# TSOC_GROVEY_I2CHUB_R1_1.net
KiCad netlist of a schematic drawn in EAGLE
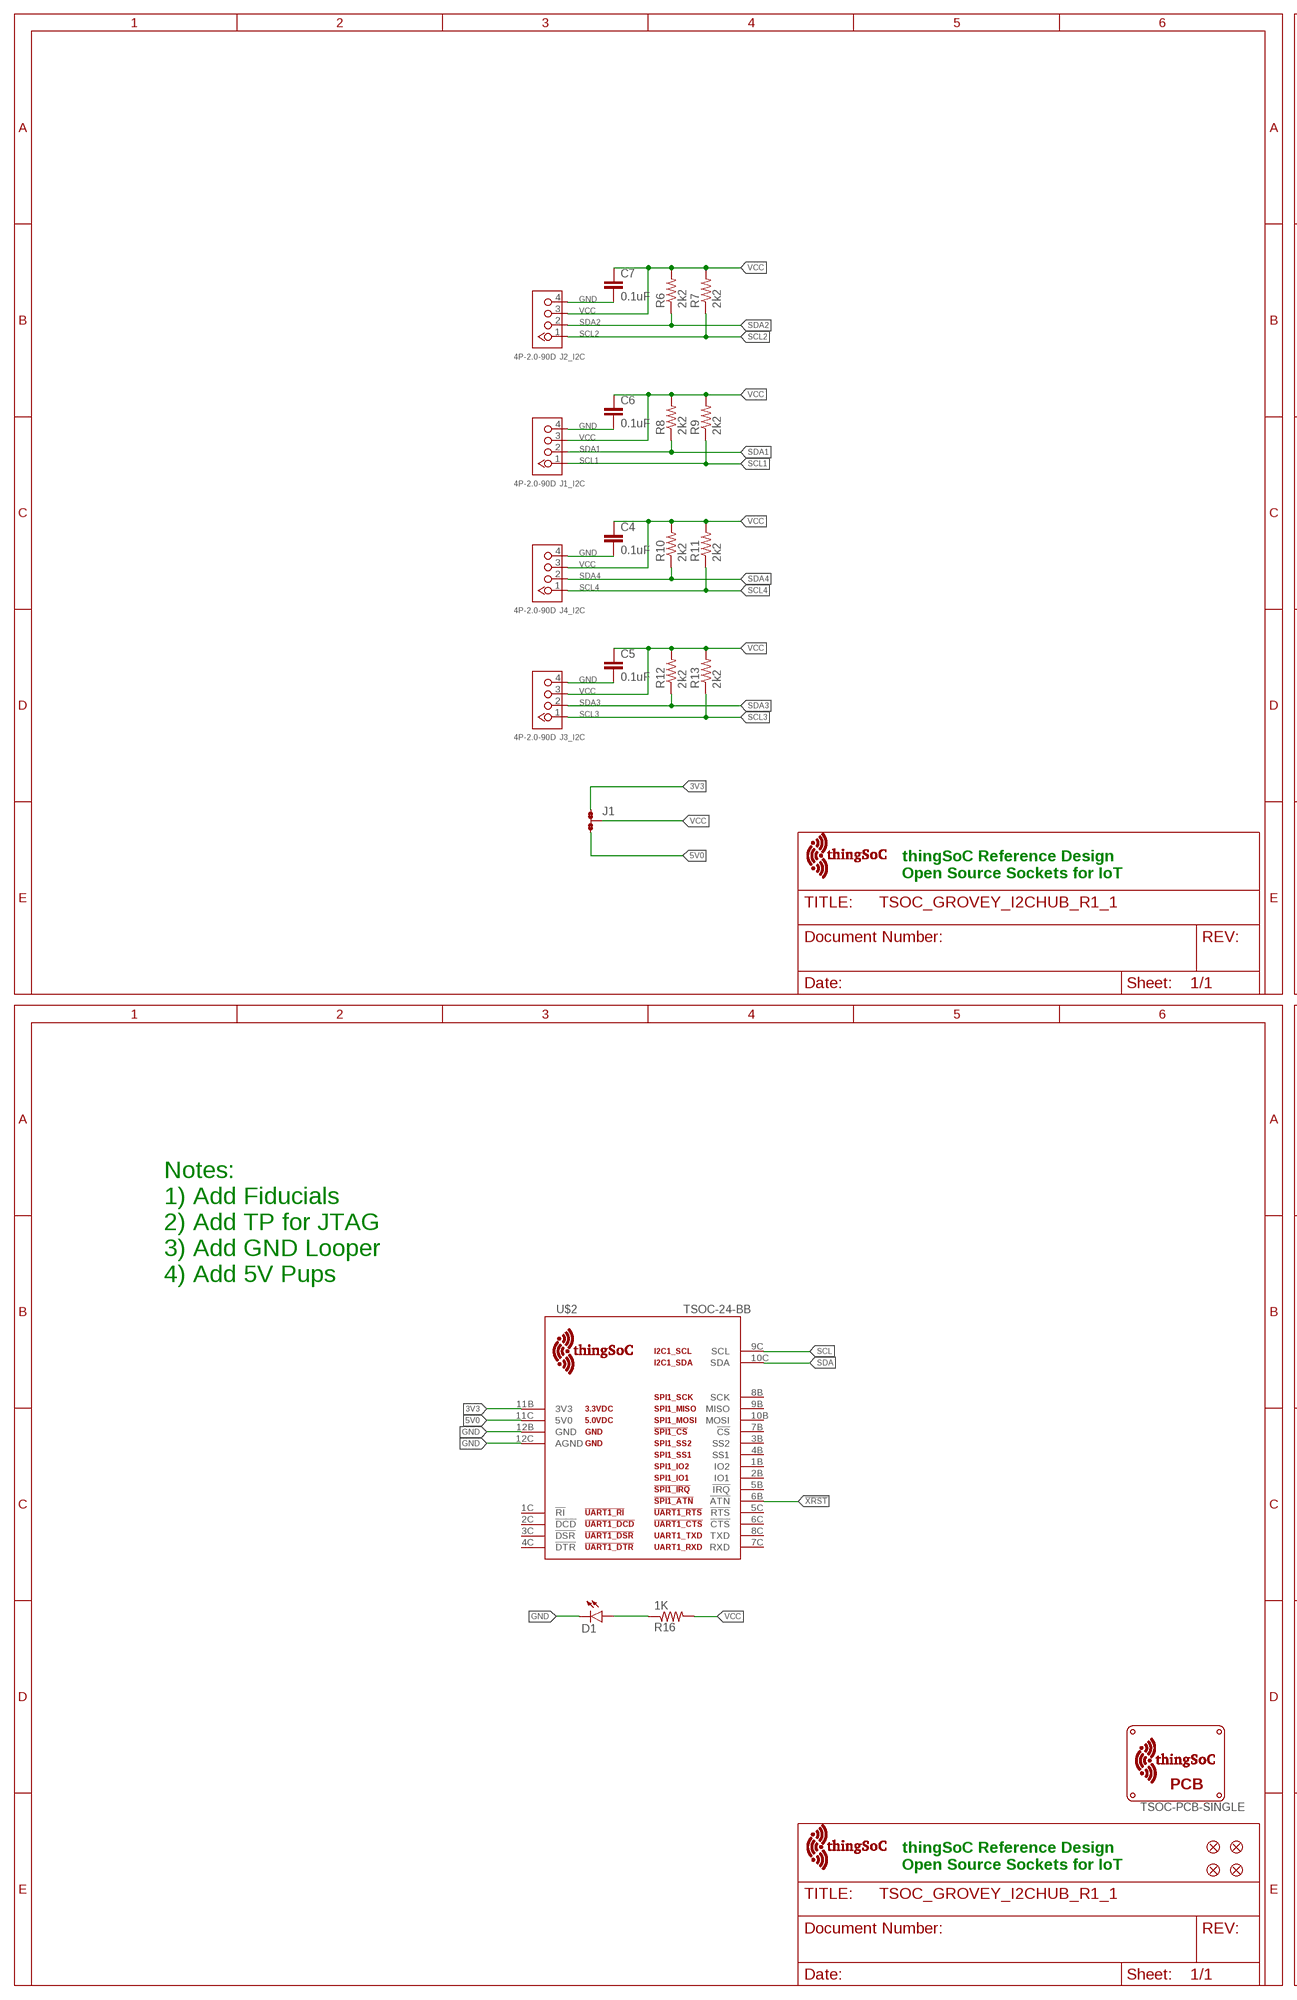
[diagram p0: schematic, sheet 1, part 1 of 2]
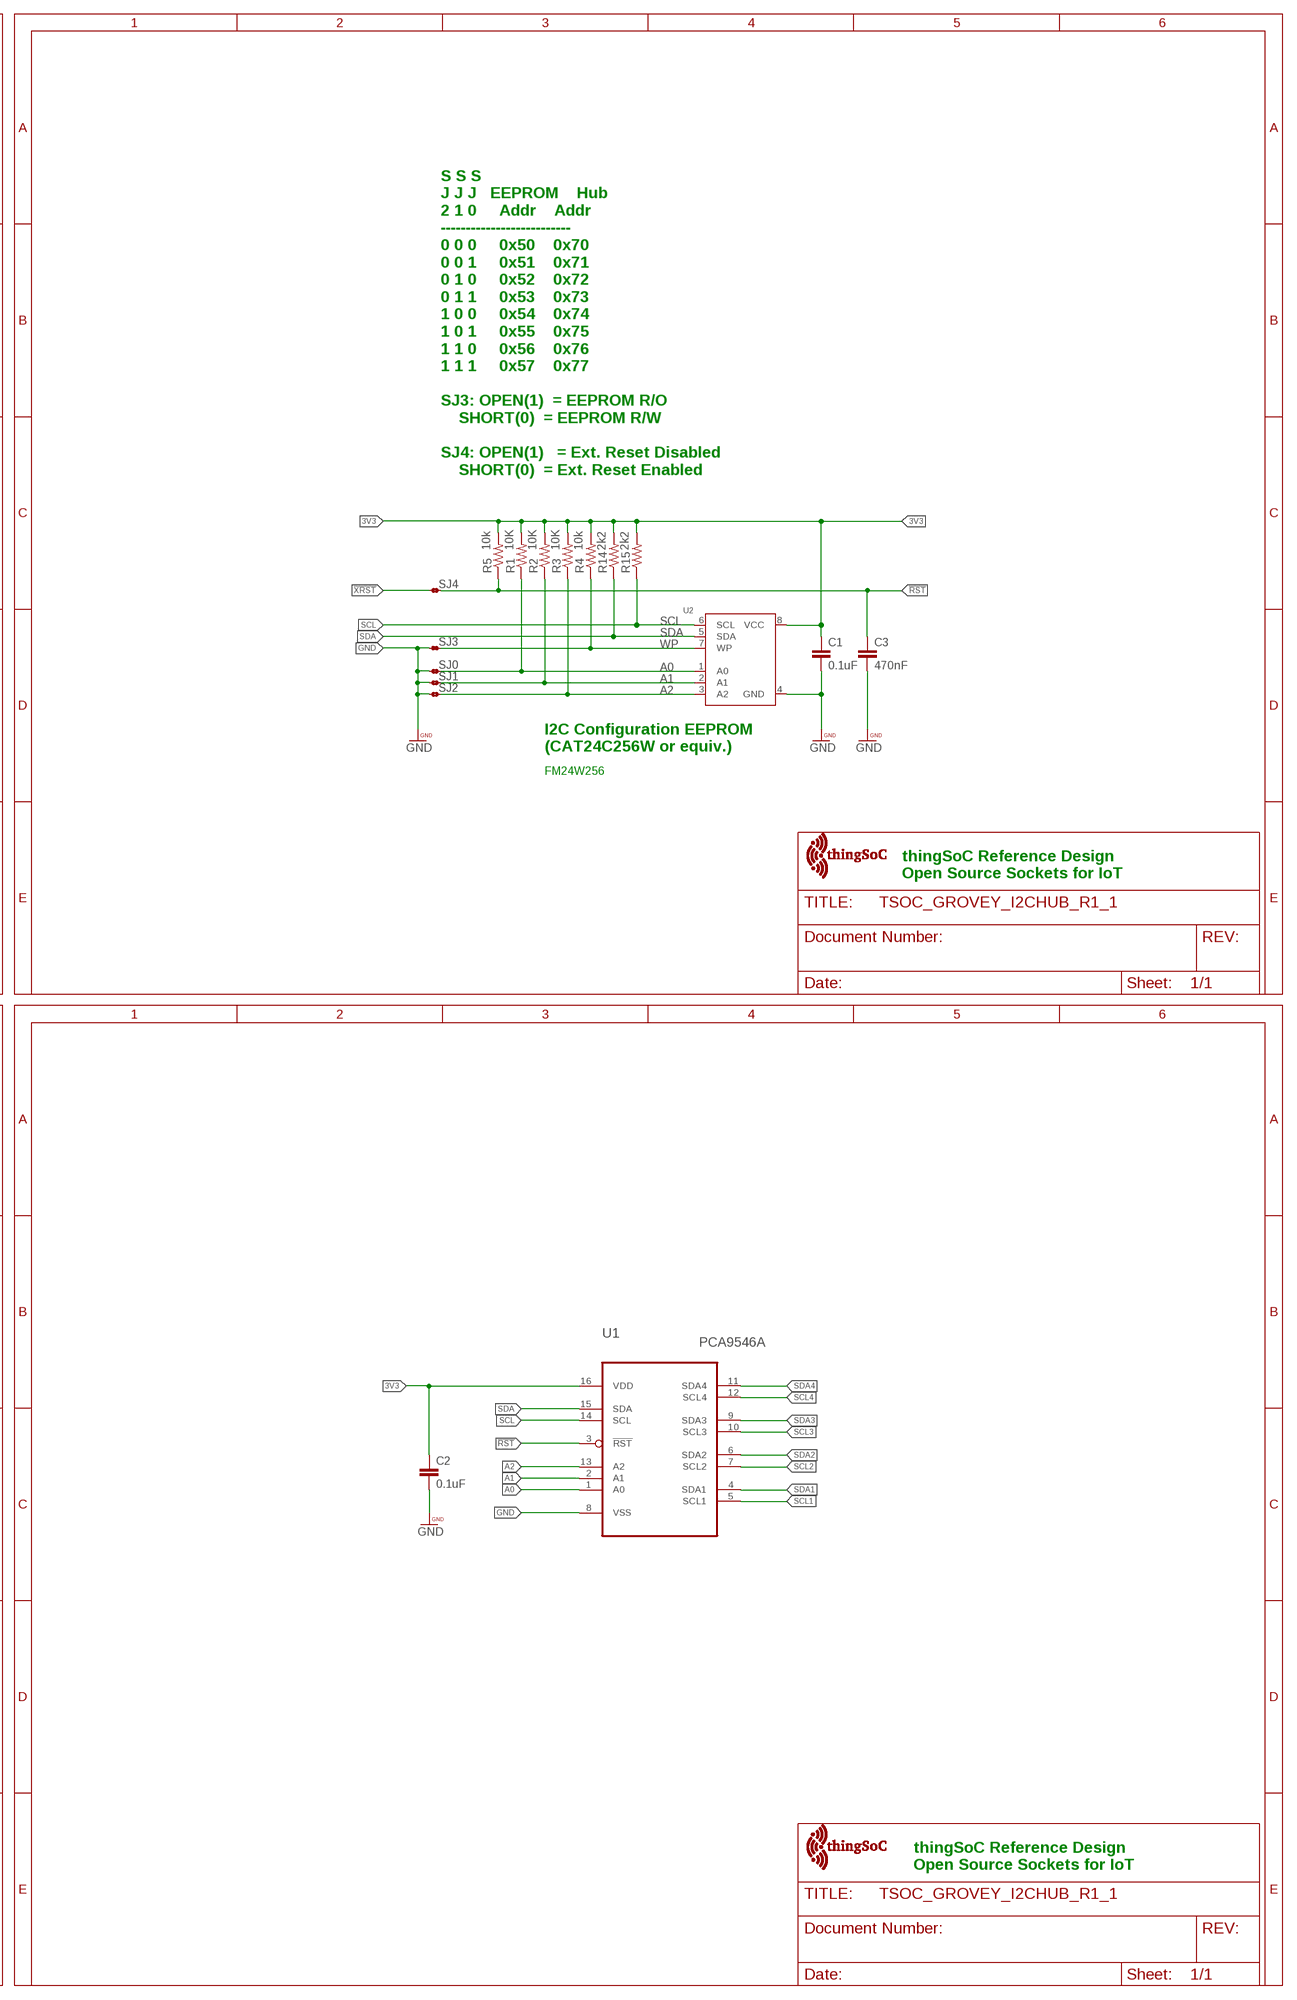
[diagram p1: schematic, sheet 1, part 2 of 2]

(export (version "E")
  (design (tool "Eeschema 10.0.6"))
  (components
    (comp (ref "C1")
      (value "0.1uF")
      (footprint "eagle-import:0603-CAP")
      (libsource (lib "eagle-import") (part "CAP0603-CAP"))
    )
    (comp (ref "C2")
      (value "0.1uF")
      (footprint "eagle-import:0603-CAP")
      (libsource (lib "eagle-import") (part "CAP0603-CAP"))
    )
    (comp (ref "C3")
      (value "470nF")
      (footprint "eagle-import:0603-CAP")
      (libsource (lib "eagle-import") (part "CAP0603-CAP"))
    )
    (comp (ref "C4")
      (value "0.1uF")
      (footprint "eagle-import:0603-CAP")
      (libsource (lib "eagle-import") (part "CAP0603-CAP"))
    )
    (comp (ref "C5")
      (value "0.1uF")
      (footprint "eagle-import:0603-CAP")
      (libsource (lib "eagle-import") (part "CAP0603-CAP"))
    )
    (comp (ref "C6")
      (value "0.1uF")
      (footprint "eagle-import:0603-CAP")
      (libsource (lib "eagle-import") (part "CAP0603-CAP"))
    )
    (comp (ref "C7")
      (value "0.1uF")
      (footprint "eagle-import:0603-CAP")
      (libsource (lib "eagle-import") (part "CAP0603-CAP"))
    )
    (comp (ref "D1")
      (value "LED0603")
      (footprint "eagle-import:LED-0603")
      (libsource (lib "eagle-import") (part "LED0603"))
    )
    (comp (ref "FID1")
      (value "FIDUCIALUFIDUCIAL")
      (footprint "eagle-import:MICRO-FIDUCIAL")
      (libsource (lib "eagle-import") (part "FIDUCIALUFIDUCIAL"))
    )
    (comp (ref "FID2")
      (value "FIDUCIALUFIDUCIAL")
      (footprint "eagle-import:MICRO-FIDUCIAL")
      (libsource (lib "eagle-import") (part "FIDUCIALUFIDUCIAL"))
    )
    (comp (ref "FID3")
      (value "FIDUCIALUFIDUCIAL")
      (footprint "eagle-import:MICRO-FIDUCIAL")
      (libsource (lib "eagle-import") (part "FIDUCIALUFIDUCIAL"))
    )
    (comp (ref "FID4")
      (value "FIDUCIALUFIDUCIAL")
      (footprint "eagle-import:MICRO-FIDUCIAL")
      (libsource (lib "eagle-import") (part "FIDUCIALUFIDUCIAL"))
    )
    (comp (ref "J1")
      (value "JMP-3-NO-PTH")
      (footprint "eagle-import:JMP-3-NO-PTH-2.54")
      (libsource (lib "eagle-import") (part "JMP-3-NO-PTH"))
    )
    (comp (ref "J1_I2C")
      (value "4P-2.0-90D")
      (footprint "eagle-import:HW4-2.0-90D")
      (libsource (lib "eagle-import") (part "GROVE-CONNECTOR-DIP-90D(4P-2.0)"))
    )
    (comp (ref "J2_I2C")
      (value "4P-2.0-90D")
      (footprint "eagle-import:HW4-2.0-90D")
      (libsource (lib "eagle-import") (part "GROVE-CONNECTOR-DIP-90D(4P-2.0)"))
    )
    (comp (ref "J3_I2C")
      (value "4P-2.0-90D")
      (footprint "eagle-import:HW4-2.0-90D")
      (libsource (lib "eagle-import") (part "GROVE-CONNECTOR-DIP-90D(4P-2.0)"))
    )
    (comp (ref "J4_I2C")
      (value "4P-2.0-90D")
      (footprint "eagle-import:HW4-2.0-90D")
      (libsource (lib "eagle-import") (part "GROVE-CONNECTOR-DIP-90D(4P-2.0)"))
    )
    (comp (ref "R1")
      (value "10K")
      (footprint "eagle-import:0603-RES")
      (libsource (lib "eagle-import") (part "RESISTOR0603-RES"))
    )
    (comp (ref "R2")
      (value "10K")
      (footprint "eagle-import:0603-RES")
      (libsource (lib "eagle-import") (part "RESISTOR0603-RES"))
    )
    (comp (ref "R3")
      (value "10K")
      (footprint "eagle-import:0603-RES")
      (libsource (lib "eagle-import") (part "RESISTOR0603-RES"))
    )
    (comp (ref "R4")
      (value "10k")
      (footprint "eagle-import:0603-RES")
      (libsource (lib "eagle-import") (part "RESISTOR0603-RES"))
    )
    (comp (ref "R5")
      (value "10k")
      (footprint "eagle-import:0603-RES")
      (libsource (lib "eagle-import") (part "RESISTOR0603-RES"))
    )
    (comp (ref "R6")
      (value "2k2")
      (footprint "eagle-import:0603-RES")
      (libsource (lib "eagle-import") (part "RESISTOR0603-RES"))
    )
    (comp (ref "R7")
      (value "2k2")
      (footprint "eagle-import:0603-RES")
      (libsource (lib "eagle-import") (part "RESISTOR0603-RES"))
    )
    (comp (ref "R8")
      (value "2k2")
      (footprint "eagle-import:0603-RES")
      (libsource (lib "eagle-import") (part "RESISTOR0603-RES"))
    )
    (comp (ref "R9")
      (value "2k2")
      (footprint "eagle-import:0603-RES")
      (libsource (lib "eagle-import") (part "RESISTOR0603-RES"))
    )
    (comp (ref "R10")
      (value "2k2")
      (footprint "eagle-import:0603-RES")
      (libsource (lib "eagle-import") (part "RESISTOR0603-RES"))
    )
    (comp (ref "R11")
      (value "2k2")
      (footprint "eagle-import:0603-RES")
      (libsource (lib "eagle-import") (part "RESISTOR0603-RES"))
    )
    (comp (ref "R12")
      (value "2k2")
      (footprint "eagle-import:0603-RES")
      (libsource (lib "eagle-import") (part "RESISTOR0603-RES"))
    )
    (comp (ref "R13")
      (value "2k2")
      (footprint "eagle-import:0603-RES")
      (libsource (lib "eagle-import") (part "RESISTOR0603-RES"))
    )
    (comp (ref "R14")
      (value "2k2")
      (footprint "eagle-import:0603-RES")
      (libsource (lib "eagle-import") (part "RESISTOR0603-RES"))
    )
    (comp (ref "R15")
      (value "2k2")
      (footprint "eagle-import:0603-RES")
      (libsource (lib "eagle-import") (part "RESISTOR0603-RES"))
    )
    (comp (ref "R16")
      (value "1K")
      (footprint "eagle-import:0603-RES")
      (libsource (lib "eagle-import") (part "RESISTOR_SFE0603-RES"))
    )
    (comp (ref "SJ0")
      (value "JMP-2-NO")
      (footprint "eagle-import:JMP-2-NO")
      (libsource (lib "eagle-import") (part "JMP-2-NO"))
    )
    (comp (ref "SJ1")
      (value "JMP-2-NO")
      (footprint "eagle-import:JMP-2-NO")
      (libsource (lib "eagle-import") (part "JMP-2-NO"))
    )
    (comp (ref "SJ2")
      (value "JMP-2-NO")
      (footprint "eagle-import:JMP-2-NO")
      (libsource (lib "eagle-import") (part "JMP-2-NO"))
    )
    (comp (ref "SJ3")
      (value "JMP-2-NC")
      (footprint "eagle-import:JMP-2-NC")
      (libsource (lib "eagle-import") (part "JMP-2-NC"))
    )
    (comp (ref "SJ4")
      (value "JMP-2-NO")
      (footprint "eagle-import:JMP-2-NO")
      (libsource (lib "eagle-import") (part "JMP-2-NO"))
    )
    (comp (ref "U$1")
      (value "TSOC-PCB-SINGLE")
      (footprint "eagle-import:TSOC-BB-BRD-DIM")
      (libsource (lib "eagle-import") (part "TSOC-PCB-SINGLE"))
    )
    (comp (ref "U$2")
      (value "TSOC-24-BB")
      (footprint "eagle-import:TSOC-BB-S24")
      (libsource (lib "eagle-import") (part "TSOC-24-BB"))
    )
    (comp (ref "U$7")
      (value "TSOC-LOGO-SMALL")
      (footprint "eagle-import:TSOC-LOGO-SML")
      (libsource (lib "eagle-import") (part "TSOC-LOGO-SMALL"))
    )
    (comp (ref "U$9")
      (value "TSOC-LOGO-SMALL")
      (footprint "eagle-import:TSOC-LOGO-SML")
      (libsource (lib "eagle-import") (part "TSOC-LOGO-SMALL"))
    )
    (comp (ref "U$100")
      (value "TSOC-LOGO-SMALL")
      (footprint "eagle-import:TSOC-LOGO-SML")
      (libsource (lib "eagle-import") (part "TSOC-LOGO-SMALL"))
    )
    (comp (ref "U$101")
      (value "TSOC-LOGO-LRG")
      (footprint "eagle-import:TSOC-LOGO-LRG")
      (libsource (lib "eagle-import") (part "TSOC-LOGO-LRG"))
    )
    (comp (ref "U1")
      (value "PCA9546A")
      (footprint "eagle-import:SOP65P640X110-16N")
      (fields (field (name "MPN") "PCA9546APW,112"))
      (libsource (lib "eagle-import") (part "PCA9546A"))
    )
    (comp (ref "U2")
      (value "EEPROM_I2C_SOIC8_GENERIC")
      (footprint "eagle-import:SOIC8_150MIL")
      (libsource (lib "eagle-import") (part "EEPROM_I2C_SOIC8_GENERIC"))
    )
  )
  (nets
    (net (code "1") (name "/WP") (class "Default")
      (node (ref "R4") (pin "1") (pinfunction "1_1") (pintype "passive"))
      (node (ref "SJ3") (pin "2") (pinfunction "2_2") (pintype "passive"))
      (node (ref "U2") (pin "7") (pinfunction "WP_7") (pintype "input"))
    )
    (net (code "2") (name "/~{RST}") (class "Default")
      (node (ref "C3") (pin "1") (pinfunction "1_1") (pintype "passive"))
      (node (ref "R5") (pin "1") (pinfunction "1_1") (pintype "passive"))
      (node (ref "SJ4") (pin "1") (pinfunction "1_1") (pintype "passive"))
      (node (ref "U1") (pin "3") (pinfunction "~{RST}_3") (pintype "input"))
    )
    (net (code "3") (name "/~{XRST}") (class "Default")
      (node (ref "SJ4") (pin "2") (pinfunction "2_2") (pintype "passive"))
      (node (ref "U$2") (pin "6B") (pinfunction "~{ATN}_6B") (pintype "bidirectional"))
    )
    (net (code "4") (name "3V3") (class "Default")
      (node (ref "C1") (pin "1") (pinfunction "1_1") (pintype "passive"))
      (node (ref "C2") (pin "1") (pinfunction "1_1") (pintype "passive"))
      (node (ref "J1") (pin "1") (pinfunction "1_1") (pintype "passive"))
      (node (ref "R1") (pin "2") (pinfunction "2_2") (pintype "passive"))
      (node (ref "R14") (pin "2") (pinfunction "2_2") (pintype "passive"))
      (node (ref "R15") (pin "2") (pinfunction "2_2") (pintype "passive"))
      (node (ref "R2") (pin "2") (pinfunction "2_2") (pintype "passive"))
      (node (ref "R3") (pin "2") (pinfunction "2_2") (pintype "passive"))
      (node (ref "R4") (pin "2") (pinfunction "2_2") (pintype "passive"))
      (node (ref "R5") (pin "2") (pinfunction "2_2") (pintype "passive"))
      (node (ref "U$2") (pin "11B") (pinfunction "3V3_11B") (pintype "bidirectional"))
      (node (ref "U1") (pin "16") (pinfunction "VDD_16") (pintype "power_in"))
      (node (ref "U2") (pin "8") (pinfunction "VCC_8") (pintype "power_in"))
    )
    (net (code "5") (name "5V0") (class "Default")
      (node (ref "J1") (pin "3") (pinfunction "3_3") (pintype "passive"))
      (node (ref "U$2") (pin "11C") (pinfunction "5V0_11C") (pintype "bidirectional"))
    )
    (net (code "6") (name "A0") (class "Default")
      (node (ref "R1") (pin "1") (pinfunction "1_1") (pintype "passive"))
      (node (ref "SJ0") (pin "2") (pinfunction "2_2") (pintype "passive"))
      (node (ref "U1") (pin "1") (pinfunction "A0_1") (pintype "input"))
      (node (ref "U2") (pin "1") (pinfunction "A0_1") (pintype "input"))
    )
    (net (code "7") (name "A1") (class "Default")
      (node (ref "R2") (pin "1") (pinfunction "1_1") (pintype "passive"))
      (node (ref "SJ1") (pin "2") (pinfunction "2_2") (pintype "passive"))
      (node (ref "U1") (pin "2") (pinfunction "A1_2") (pintype "input"))
      (node (ref "U2") (pin "2") (pinfunction "A1_2") (pintype "input"))
    )
    (net (code "8") (name "A2") (class "Default")
      (node (ref "R3") (pin "1") (pinfunction "1_1") (pintype "passive"))
      (node (ref "SJ2") (pin "2") (pinfunction "2_2") (pintype "passive"))
      (node (ref "U1") (pin "13") (pinfunction "A2_13") (pintype "input"))
      (node (ref "U2") (pin "3") (pinfunction "A2_3") (pintype "input"))
    )
    (net (code "9") (name "GND") (class "Default")
      (node (ref "C1") (pin "2") (pinfunction "2_2") (pintype "passive"))
      (node (ref "C2") (pin "2") (pinfunction "2_2") (pintype "passive"))
      (node (ref "C3") (pin "2") (pinfunction "2_2") (pintype "passive"))
      (node (ref "C4") (pin "2") (pinfunction "2_2") (pintype "passive"))
      (node (ref "C5") (pin "2") (pinfunction "2_2") (pintype "passive"))
      (node (ref "C6") (pin "2") (pinfunction "2_2") (pintype "passive"))
      (node (ref "C7") (pin "2") (pinfunction "2_2") (pintype "passive"))
      (node (ref "D1") (pin "C") (pinfunction "C_C") (pintype "passive"))
      (node (ref "J1_I2C") (pin "4") (pinfunction "4_4") (pintype "bidirectional"))
      (node (ref "J2_I2C") (pin "4") (pinfunction "4_4") (pintype "bidirectional"))
      (node (ref "J3_I2C") (pin "4") (pinfunction "4_4") (pintype "bidirectional"))
      (node (ref "J4_I2C") (pin "4") (pinfunction "4_4") (pintype "bidirectional"))
      (node (ref "SJ0") (pin "1") (pinfunction "1_1") (pintype "passive"))
      (node (ref "SJ1") (pin "1") (pinfunction "1_1") (pintype "passive"))
      (node (ref "SJ2") (pin "1") (pinfunction "1_1") (pintype "passive"))
      (node (ref "SJ3") (pin "1") (pinfunction "1_1") (pintype "passive"))
      (node (ref "U$2") (pin "12B") (pinfunction "GND_12B") (pintype "bidirectional"))
      (node (ref "U$2") (pin "12C") (pinfunction "AGND_12C") (pintype "bidirectional"))
      (node (ref "U1") (pin "8") (pinfunction "VSS_8") (pintype "passive"))
      (node (ref "U2") (pin "4") (pinfunction "GND_4") (pintype "power_in"))
    )
    (net (code "10") (name "Net-(D1-PadA)") (class "Default")
      (node (ref "D1") (pin "A") (pinfunction "A_A") (pintype "passive"))
      (node (ref "R16") (pin "1") (pinfunction "1_1") (pintype "passive"))
    )
    (net (code "11") (name "SCL") (class "Default")
      (node (ref "R15") (pin "1") (pinfunction "1_1") (pintype "passive"))
      (node (ref "U$2") (pin "9C") (pinfunction "SCL_9C") (pintype "bidirectional"))
      (node (ref "U1") (pin "14") (pinfunction "SCL_14") (pintype "bidirectional"))
      (node (ref "U2") (pin "6") (pinfunction "SCL_6") (pintype "input"))
    )
    (net (code "12") (name "SCL1") (class "Default")
      (node (ref "J1_I2C") (pin "1") (pinfunction "1_1") (pintype "bidirectional"))
      (node (ref "R9") (pin "1") (pinfunction "1_1") (pintype "passive"))
      (node (ref "U1") (pin "5") (pinfunction "SCL1_5") (pintype "input"))
    )
    (net (code "13") (name "SCL2") (class "Default")
      (node (ref "J2_I2C") (pin "1") (pinfunction "1_1") (pintype "bidirectional"))
      (node (ref "R7") (pin "1") (pinfunction "1_1") (pintype "passive"))
      (node (ref "U1") (pin "7") (pinfunction "SCL2_7") (pintype "input"))
    )
    (net (code "14") (name "SCL3") (class "Default")
      (node (ref "J3_I2C") (pin "1") (pinfunction "1_1") (pintype "bidirectional"))
      (node (ref "R13") (pin "1") (pinfunction "1_1") (pintype "passive"))
      (node (ref "U1") (pin "10") (pinfunction "SCL3_10") (pintype "input"))
    )
    (net (code "15") (name "SCL4") (class "Default")
      (node (ref "J4_I2C") (pin "1") (pinfunction "1_1") (pintype "bidirectional"))
      (node (ref "R11") (pin "1") (pinfunction "1_1") (pintype "passive"))
      (node (ref "U1") (pin "12") (pinfunction "SCL4_12") (pintype "input"))
    )
    (net (code "16") (name "SDA") (class "Default")
      (node (ref "R14") (pin "1") (pinfunction "1_1") (pintype "passive"))
      (node (ref "U$2") (pin "10C") (pinfunction "SDA_10C") (pintype "bidirectional"))
      (node (ref "U1") (pin "15") (pinfunction "SDA_15") (pintype "bidirectional"))
      (node (ref "U2") (pin "5") (pinfunction "SDA_5") (pintype "bidirectional"))
    )
    (net (code "17") (name "SDA1") (class "Default")
      (node (ref "J1_I2C") (pin "2") (pinfunction "2_2") (pintype "bidirectional"))
      (node (ref "R8") (pin "1") (pinfunction "1_1") (pintype "passive"))
      (node (ref "U1") (pin "4") (pinfunction "SDA1_4") (pintype "input"))
    )
    (net (code "18") (name "SDA2") (class "Default")
      (node (ref "J2_I2C") (pin "2") (pinfunction "2_2") (pintype "bidirectional"))
      (node (ref "R6") (pin "1") (pinfunction "1_1") (pintype "passive"))
      (node (ref "U1") (pin "6") (pinfunction "SDA2_6") (pintype "input"))
    )
    (net (code "19") (name "SDA3") (class "Default")
      (node (ref "J3_I2C") (pin "2") (pinfunction "2_2") (pintype "bidirectional"))
      (node (ref "R12") (pin "1") (pinfunction "1_1") (pintype "passive"))
      (node (ref "U1") (pin "9") (pinfunction "SDA3_9") (pintype "input"))
    )
    (net (code "20") (name "SDA4") (class "Default")
      (node (ref "J4_I2C") (pin "2") (pinfunction "2_2") (pintype "bidirectional"))
      (node (ref "R10") (pin "1") (pinfunction "1_1") (pintype "passive"))
      (node (ref "U1") (pin "11") (pinfunction "SDA4_11") (pintype "input"))
    )
    (net (code "21") (name "VCC") (class "Default")
      (node (ref "C4") (pin "1") (pinfunction "1_1") (pintype "passive"))
      (node (ref "C5") (pin "1") (pinfunction "1_1") (pintype "passive"))
      (node (ref "C6") (pin "1") (pinfunction "1_1") (pintype "passive"))
      (node (ref "C7") (pin "1") (pinfunction "1_1") (pintype "passive"))
      (node (ref "J1") (pin "2") (pinfunction "2_2") (pintype "passive"))
      (node (ref "J1_I2C") (pin "3") (pinfunction "3_3") (pintype "bidirectional"))
      (node (ref "J2_I2C") (pin "3") (pinfunction "3_3") (pintype "bidirectional"))
      (node (ref "J3_I2C") (pin "3") (pinfunction "3_3") (pintype "bidirectional"))
      (node (ref "J4_I2C") (pin "3") (pinfunction "3_3") (pintype "bidirectional"))
      (node (ref "R10") (pin "2") (pinfunction "2_2") (pintype "passive"))
      (node (ref "R11") (pin "2") (pinfunction "2_2") (pintype "passive"))
      (node (ref "R12") (pin "2") (pinfunction "2_2") (pintype "passive"))
      (node (ref "R13") (pin "2") (pinfunction "2_2") (pintype "passive"))
      (node (ref "R16") (pin "2") (pinfunction "2_2") (pintype "passive"))
      (node (ref "R6") (pin "2") (pinfunction "2_2") (pintype "passive"))
      (node (ref "R7") (pin "2") (pinfunction "2_2") (pintype "passive"))
      (node (ref "R8") (pin "2") (pinfunction "2_2") (pintype "passive"))
      (node (ref "R9") (pin "2") (pinfunction "2_2") (pintype "passive"))
    )
    (net (code "22") (name "unconnected-(U$2-IO1-Pad2B)") (class "Default")
      (node (ref "U$2") (pin "2B") (pinfunction "IO1_2B") (pintype "bidirectional"))
    )
    (net (code "23") (name "unconnected-(U$2-IO2-Pad1B)") (class "Default")
      (node (ref "U$2") (pin "1B") (pinfunction "IO2_1B") (pintype "bidirectional"))
    )
    (net (code "24") (name "unconnected-(U$2-MISO-Pad9B)") (class "Default")
      (node (ref "U$2") (pin "9B") (pinfunction "MISO_9B") (pintype "bidirectional"))
    )
    (net (code "25") (name "unconnected-(U$2-MOSI-Pad10B)") (class "Default")
      (node (ref "U$2") (pin "10B") (pinfunction "MOSI_10B") (pintype "bidirectional"))
    )
    (net (code "26") (name "unconnected-(U$2-RXD-Pad7C)") (class "Default")
      (node (ref "U$2") (pin "7C") (pinfunction "RXD_7C") (pintype "bidirectional"))
    )
    (net (code "27") (name "unconnected-(U$2-SCK-Pad8B)") (class "Default")
      (node (ref "U$2") (pin "8B") (pinfunction "SCK_8B") (pintype "bidirectional"))
    )
    (net (code "28") (name "unconnected-(U$2-SS1-Pad4B)") (class "Default")
      (node (ref "U$2") (pin "4B") (pinfunction "SS1_4B") (pintype "bidirectional"))
    )
    (net (code "29") (name "unconnected-(U$2-SS2-Pad3B)") (class "Default")
      (node (ref "U$2") (pin "3B") (pinfunction "SS2_3B") (pintype "bidirectional"))
    )
    (net (code "30") (name "unconnected-(U$2-TXD-Pad8C)") (class "Default")
      (node (ref "U$2") (pin "8C") (pinfunction "TXD_8C") (pintype "bidirectional"))
    )
    (net (code "31") (name "unconnected-(U$2-~{CS}-Pad7B)") (class "Default")
      (node (ref "U$2") (pin "7B") (pinfunction "~{CS}_7B") (pintype "bidirectional"))
    )
    (net (code "32") (name "unconnected-(U$2-~{CTS}-Pad6C)") (class "Default")
      (node (ref "U$2") (pin "6C") (pinfunction "~{CTS}_6C") (pintype "bidirectional"))
    )
    (net (code "33") (name "unconnected-(U$2-~{DCD}-Pad2C)") (class "Default")
      (node (ref "U$2") (pin "2C") (pinfunction "~{DCD}_2C") (pintype "bidirectional"))
    )
    (net (code "34") (name "unconnected-(U$2-~{DSR}-Pad3C)") (class "Default")
      (node (ref "U$2") (pin "3C") (pinfunction "~{DSR}_3C") (pintype "bidirectional"))
    )
    (net (code "35") (name "unconnected-(U$2-~{DTR}-Pad4C)") (class "Default")
      (node (ref "U$2") (pin "4C") (pinfunction "~{DTR}_4C") (pintype "bidirectional"))
    )
    (net (code "36") (name "unconnected-(U$2-~{IRQ}-Pad5B)") (class "Default")
      (node (ref "U$2") (pin "5B") (pinfunction "~{IRQ}_5B") (pintype "bidirectional"))
    )
    (net (code "37") (name "unconnected-(U$2-~{RI}-Pad1C)") (class "Default")
      (node (ref "U$2") (pin "1C") (pinfunction "~{RI}_1C") (pintype "bidirectional"))
    )
    (net (code "38") (name "unconnected-(U$2-~{RTS}-Pad5C)") (class "Default")
      (node (ref "U$2") (pin "5C") (pinfunction "~{RTS}_5C") (pintype "bidirectional"))
    )
  )
)
